# BLEduino_Shield-Shield.net
KiCad netlist of a schematic drawn in EAGLE
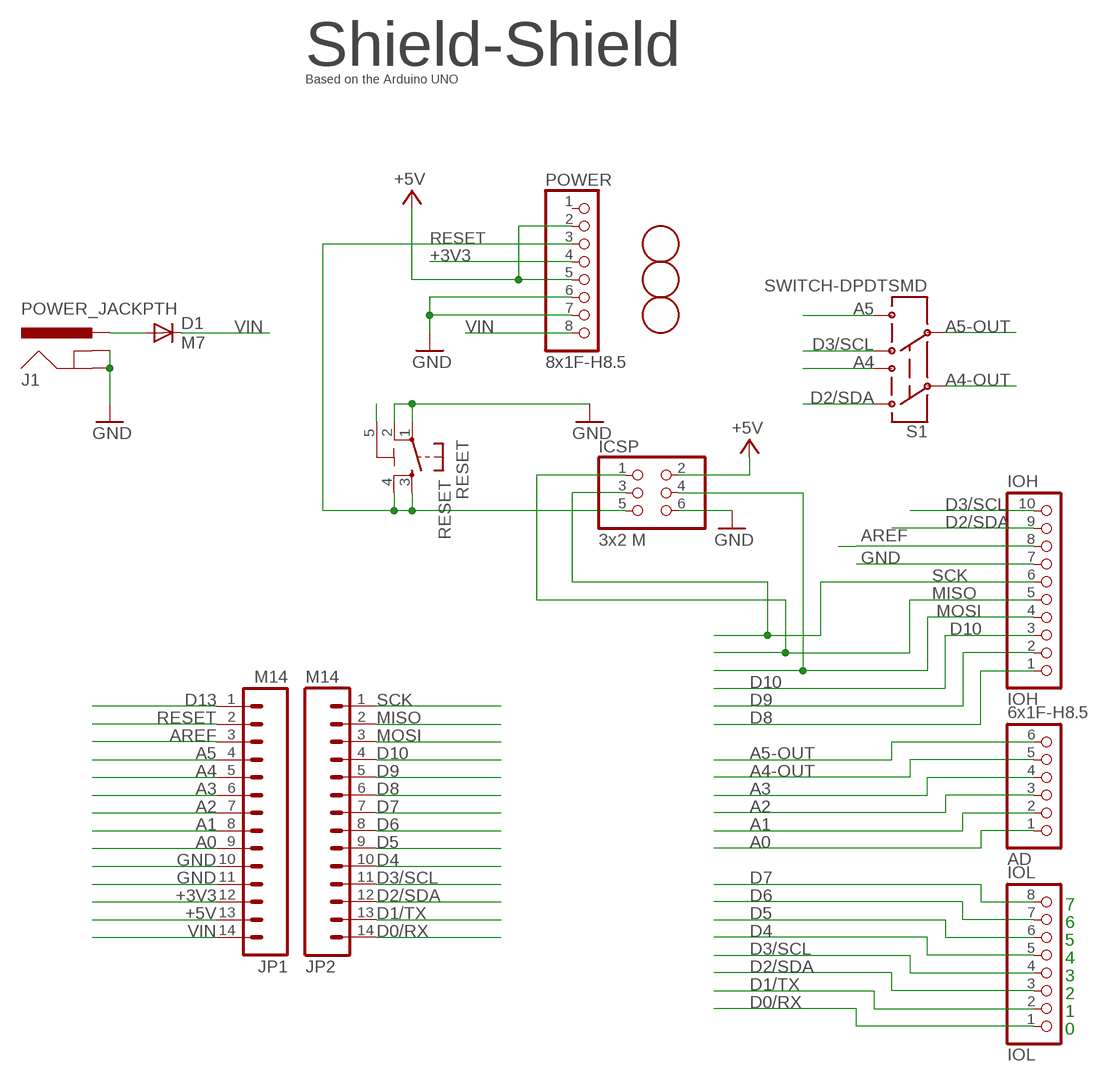
[diagram p0: schematic, sheet 1]

(export (version "E")
  (design (tool "Eeschema 10.0.6"))
  (components
    (comp (ref "AD")
      (value "6x1F-H8.5")
      (footprint "eagle-import:1X06")
      (libsource (lib "eagle-import") (part "PINHD-1X6"))
    )
    (comp (ref "D1")
      (value "M7")
      (footprint "eagle-import:SMB")
      (libsource (lib "eagle-import") (part "DIODE-SMB"))
    )
    (comp (ref "FD1")
      (value "FIDUCIALMOUNT")
      (footprint "eagle-import:FIDUCIA-MOUNT")
      (libsource (lib "eagle-import") (part "FIDUCIALMOUNT"))
    )
    (comp (ref "FD2")
      (value "FIDUCIALMOUNT")
      (footprint "eagle-import:FIDUCIA-MOUNT")
      (libsource (lib "eagle-import") (part "FIDUCIALMOUNT"))
    )
    (comp (ref "FD3")
      (value "FIDUCIALMOUNT")
      (footprint "eagle-import:FIDUCIA-MOUNT")
      (libsource (lib "eagle-import") (part "FIDUCIALMOUNT"))
    )
    (comp (ref "ICSP")
      (value "3x2 M")
      (footprint "eagle-import:2X03")
      (libsource (lib "eagle-import") (part "PINHD-2X3"))
    )
    (comp (ref "IOH")
      (value "IOH")
      (footprint "eagle-import:1X10")
      (libsource (lib "eagle-import") (part "PINHD-1X10_ARD"))
    )
    (comp (ref "IOL")
      (value "IOL")
      (footprint "eagle-import:1X08")
      (libsource (lib "eagle-import") (part "PINHD-1X8"))
    )
    (comp (ref "J1")
      (value "POWER_JACKPTH")
      (footprint "eagle-import:POWER_JACK_PTH")
      (libsource (lib "eagle-import") (part "POWER_JACKPTH"))
    )
    (comp (ref "JP1")
      (value "M14")
      (footprint "eagle-import:1X14")
      (libsource (lib "eagle-import") (part "M14"))
    )
    (comp (ref "JP2")
      (value "M14")
      (footprint "eagle-import:1X14")
      (libsource (lib "eagle-import") (part "M14"))
    )
    (comp (ref "POWER")
      (value "8x1F-H8.5")
      (footprint "eagle-import:1X08")
      (libsource (lib "eagle-import") (part "PINHD-1X8"))
    )
    (comp (ref "RESET")
      (value "RESET")
      (footprint "eagle-import:TS42")
      (libsource (lib "eagle-import") (part "TS42"))
    )
    (comp (ref "S1")
      (value "SWITCH-DPDTSMD")
      (footprint "eagle-import:AYZ0202")
      (libsource (lib "eagle-import") (part "SWITCH-DPDTSMD"))
    )
  )
  (nets
    (net (code "1") (name "+5V") (class "Default")
      (node (ref "ICSP") (pin "2") (pinfunction "2_2") (pintype "passive"))
      (node (ref "JP1") (pin "13") (pinfunction "13_13") (pintype "passive"))
      (node (ref "POWER") (pin "2") (pinfunction "2_2") (pintype "passive"))
      (node (ref "POWER") (pin "5") (pinfunction "5_5") (pintype "passive"))
    )
    (net (code "2") (name "/+3V3") (class "Default")
      (node (ref "JP1") (pin "12") (pinfunction "12_12") (pintype "passive"))
      (node (ref "POWER") (pin "4") (pinfunction "4_4") (pintype "passive"))
    )
    (net (code "3") (name "/A0") (class "Default")
      (node (ref "AD") (pin "1") (pinfunction "1_1") (pintype "passive"))
      (node (ref "JP1") (pin "9") (pinfunction "9_9") (pintype "passive"))
    )
    (net (code "4") (name "/A1") (class "Default")
      (node (ref "AD") (pin "2") (pinfunction "2_2") (pintype "passive"))
      (node (ref "JP1") (pin "8") (pinfunction "8_8") (pintype "passive"))
    )
    (net (code "5") (name "/A2") (class "Default")
      (node (ref "AD") (pin "3") (pinfunction "3_3") (pintype "passive"))
      (node (ref "JP1") (pin "7") (pinfunction "7_7") (pintype "passive"))
    )
    (net (code "6") (name "/A3") (class "Default")
      (node (ref "AD") (pin "4") (pinfunction "4_4") (pintype "passive"))
      (node (ref "JP1") (pin "6") (pinfunction "6_6") (pintype "passive"))
    )
    (net (code "7") (name "/A4") (class "Default")
      (node (ref "JP1") (pin "5") (pinfunction "5_5") (pintype "passive"))
      (node (ref "S1") (pin "3") (pinfunction "3_3") (pintype "bidirectional"))
    )
    (net (code "8") (name "/A4-OUT") (class "Default")
      (node (ref "AD") (pin "5") (pinfunction "5_5") (pintype "passive"))
      (node (ref "S1") (pin "2") (pinfunction "2_2") (pintype "bidirectional"))
    )
    (net (code "9") (name "/A5") (class "Default")
      (node (ref "JP1") (pin "4") (pinfunction "4_4") (pintype "passive"))
      (node (ref "S1") (pin "6") (pinfunction "6_6") (pintype "bidirectional"))
    )
    (net (code "10") (name "/A5-OUT") (class "Default")
      (node (ref "AD") (pin "6") (pinfunction "6_6") (pintype "passive"))
      (node (ref "S1") (pin "5") (pinfunction "5_5") (pintype "bidirectional"))
    )
    (net (code "11") (name "/AREF") (class "Default")
      (node (ref "IOH") (pin "8") (pinfunction "8_8") (pintype "passive"))
      (node (ref "JP1") (pin "3") (pinfunction "3_3") (pintype "passive"))
    )
    (net (code "12") (name "/D0{slash}RX") (class "Default")
      (node (ref "IOL") (pin "1") (pinfunction "1_1") (pintype "passive"))
      (node (ref "JP2") (pin "14") (pinfunction "14_14") (pintype "passive"))
    )
    (net (code "13") (name "/D1{slash}TX") (class "Default")
      (node (ref "IOL") (pin "2") (pinfunction "2_2") (pintype "passive"))
      (node (ref "JP2") (pin "13") (pinfunction "13_13") (pintype "passive"))
    )
    (net (code "14") (name "/D2{slash}SDA") (class "Default")
      (node (ref "IOH") (pin "9") (pinfunction "9_9") (pintype "passive"))
      (node (ref "IOL") (pin "3") (pinfunction "3_3") (pintype "passive"))
      (node (ref "JP2") (pin "12") (pinfunction "12_12") (pintype "passive"))
      (node (ref "S1") (pin "1") (pinfunction "1_1") (pintype "bidirectional"))
    )
    (net (code "15") (name "/D3{slash}SCL") (class "Default")
      (node (ref "IOH") (pin "10") (pinfunction "10_10") (pintype "passive"))
      (node (ref "IOL") (pin "4") (pinfunction "4_4") (pintype "passive"))
      (node (ref "JP2") (pin "11") (pinfunction "11_11") (pintype "passive"))
      (node (ref "S1") (pin "4") (pinfunction "4_4") (pintype "bidirectional"))
    )
    (net (code "16") (name "/D4") (class "Default")
      (node (ref "IOL") (pin "5") (pinfunction "5_5") (pintype "passive"))
      (node (ref "JP2") (pin "10") (pinfunction "10_10") (pintype "passive"))
    )
    (net (code "17") (name "/D5") (class "Default")
      (node (ref "IOL") (pin "6") (pinfunction "6_6") (pintype "passive"))
      (node (ref "JP2") (pin "9") (pinfunction "9_9") (pintype "passive"))
    )
    (net (code "18") (name "/D6") (class "Default")
      (node (ref "IOL") (pin "7") (pinfunction "7_7") (pintype "passive"))
      (node (ref "JP2") (pin "8") (pinfunction "8_8") (pintype "passive"))
    )
    (net (code "19") (name "/D7") (class "Default")
      (node (ref "IOL") (pin "8") (pinfunction "8_8") (pintype "passive"))
      (node (ref "JP2") (pin "7") (pinfunction "7_7") (pintype "passive"))
    )
    (net (code "20") (name "/D8") (class "Default")
      (node (ref "IOH") (pin "1") (pinfunction "1_1") (pintype "passive"))
      (node (ref "JP2") (pin "6") (pinfunction "6_6") (pintype "passive"))
    )
    (net (code "21") (name "/D9") (class "Default")
      (node (ref "IOH") (pin "2") (pinfunction "2_2") (pintype "passive"))
      (node (ref "JP2") (pin "5") (pinfunction "5_5") (pintype "passive"))
    )
    (net (code "22") (name "/D10") (class "Default")
      (node (ref "IOH") (pin "3") (pinfunction "3_3") (pintype "passive"))
      (node (ref "JP2") (pin "4") (pinfunction "4_4") (pintype "passive"))
    )
    (net (code "23") (name "/D13") (class "Default")
      (node (ref "JP1") (pin "1") (pinfunction "1_1") (pintype "passive"))
    )
    (net (code "24") (name "/MISO") (class "Default")
      (node (ref "ICSP") (pin "1") (pinfunction "1_1") (pintype "passive"))
      (node (ref "IOH") (pin "5") (pinfunction "5_5") (pintype "passive"))
      (node (ref "JP2") (pin "2") (pinfunction "2_2") (pintype "passive"))
    )
    (net (code "25") (name "/MOSI") (class "Default")
      (node (ref "ICSP") (pin "4") (pinfunction "4_4") (pintype "passive"))
      (node (ref "IOH") (pin "4") (pinfunction "4_4") (pintype "passive"))
      (node (ref "JP2") (pin "3") (pinfunction "3_3") (pintype "passive"))
    )
    (net (code "26") (name "/RESET") (class "Default")
      (node (ref "ICSP") (pin "5") (pinfunction "5_5") (pintype "passive"))
      (node (ref "JP1") (pin "2") (pinfunction "2_2") (pintype "passive"))
      (node (ref "POWER") (pin "3") (pinfunction "3_3") (pintype "passive"))
      (node (ref "RESET") (pin "3") (pinfunction "3_3") (pintype "passive"))
      (node (ref "RESET") (pin "4") (pinfunction "4_4") (pintype "passive"))
    )
    (net (code "27") (name "/SCK") (class "Default")
      (node (ref "ICSP") (pin "3") (pinfunction "3_3") (pintype "passive"))
      (node (ref "IOH") (pin "6") (pinfunction "6_6") (pintype "passive"))
      (node (ref "JP2") (pin "1") (pinfunction "1_1") (pintype "passive"))
    )
    (net (code "28") (name "/VIN") (class "Default")
      (node (ref "D1") (pin "C") (pinfunction "C_C") (pintype "passive"))
      (node (ref "JP1") (pin "14") (pinfunction "14_14") (pintype "passive"))
      (node (ref "POWER") (pin "8") (pinfunction "8_8") (pintype "passive"))
    )
    (net (code "29") (name "GND") (class "Default")
      (node (ref "ICSP") (pin "6") (pinfunction "6_6") (pintype "passive"))
      (node (ref "IOH") (pin "7") (pinfunction "7_7") (pintype "passive"))
      (node (ref "J1") (pin "GND") (pinfunction "GND_GND") (pintype "bidirectional"))
      (node (ref "J1") (pin "GNDBREAK") (pinfunction "GNDBREAK_GNDBREAK") (pintype "bidirectional"))
      (node (ref "JP1") (pin "10") (pinfunction "10_10") (pintype "passive"))
      (node (ref "JP1") (pin "11") (pinfunction "11_11") (pintype "passive"))
      (node (ref "POWER") (pin "6") (pinfunction "6_6") (pintype "passive"))
      (node (ref "POWER") (pin "7") (pinfunction "7_7") (pintype "passive"))
      (node (ref "RESET") (pin "1") (pinfunction "1_1") (pintype "passive"))
      (node (ref "RESET") (pin "2") (pinfunction "2_2") (pintype "passive"))
    )
    (net (code "30") (name "Net-(D1-PadA)") (class "Default")
      (node (ref "D1") (pin "A") (pinfunction "A_A") (pintype "passive"))
      (node (ref "J1") (pin "PWR") (pinfunction "PWR_PWR") (pintype "bidirectional"))
    )
    (net (code "31") (name "unconnected-(POWER-Pad1)") (class "Default")
      (node (ref "POWER") (pin "1") (pinfunction "1_1") (pintype "passive"))
    )
    (net (code "32") (name "unconnected-(RESET-5-GND-Pad5)") (class "Default")
      (node (ref "RESET") (pin "5") (pinfunction "5-GND_5") (pintype "power_in"))
    )
  )
)
